# Modulo_MotorDC.net
KiCad netlist of a schematic drawn in Altium Designer
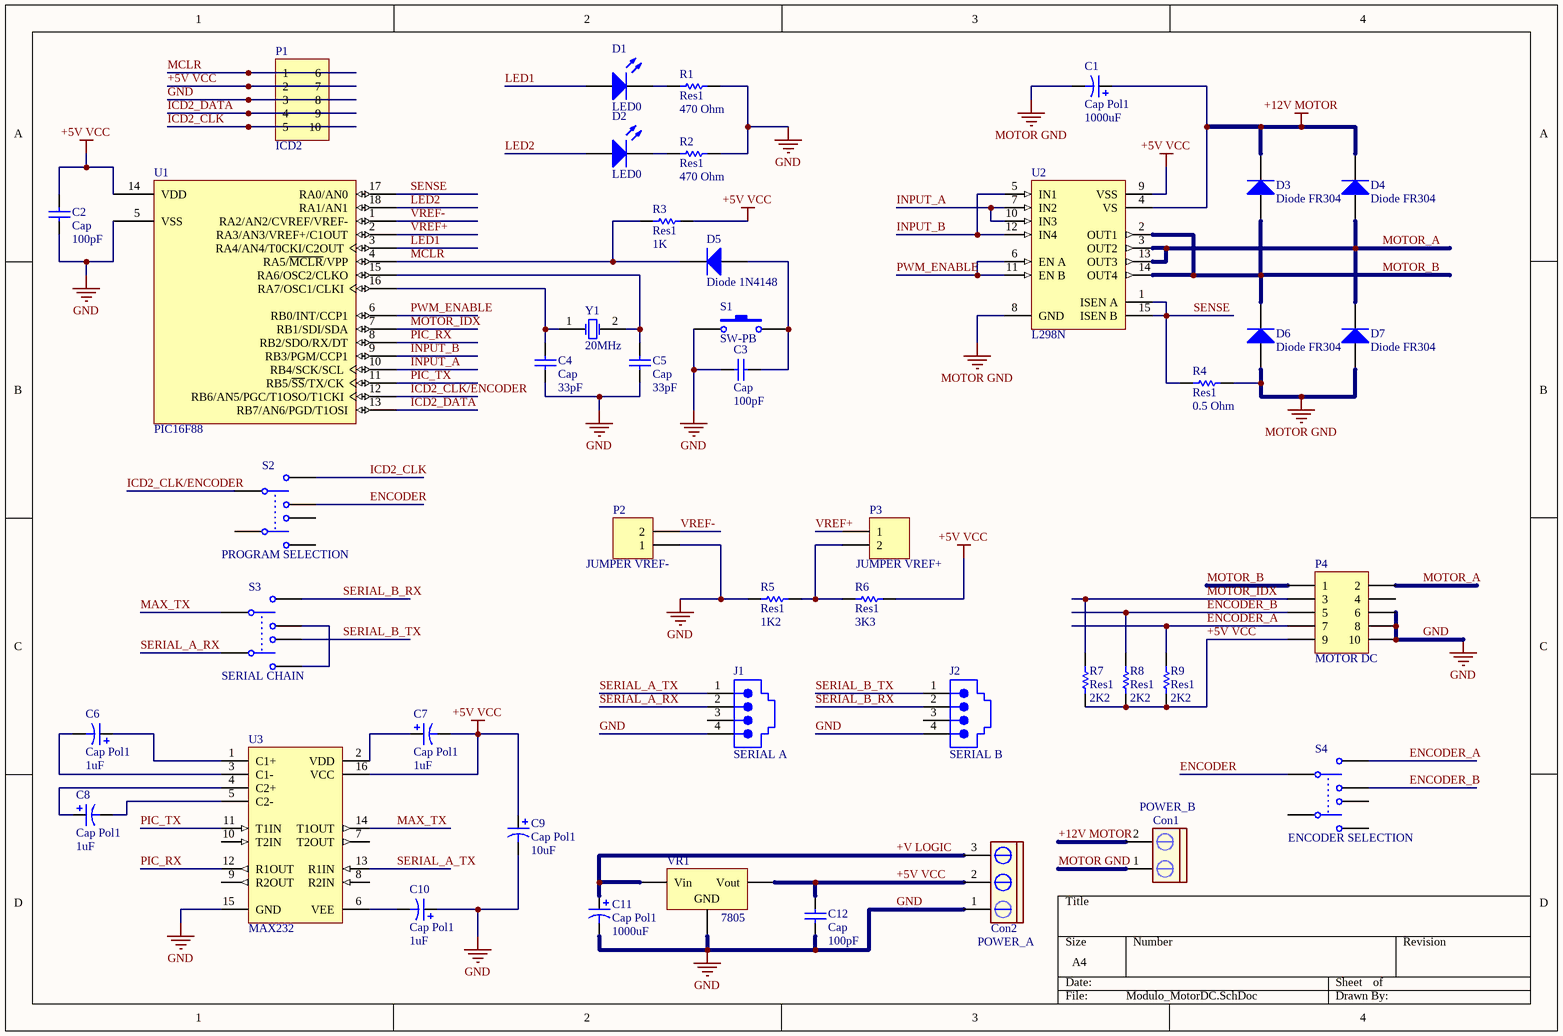
[diagram p0: Modulo_MotorDC.SchDoc]

(export (version "E")
  (design (tool "Eeschema 10.0.6"))
  (components
    (comp (ref "C1")
      (value "Cap Pol1")
      (footprint "RB5-10.5")
      (description "Polarized Capacitor (Radial)")
      (fields (field (name "ALTIUM_VALUE") "1000uF") (field (name "PUBLISHER") "Altium Limited"))
      (libsource (lib "Miscellaneous Devices") (part "Cap Pol1"))
    )
    (comp (ref "C2")
      (value "Cap")
      (footprint "CAPR2.54-5.1x3.2")
      (description "Capacitor")
      (fields (field (name "ALTIUM_VALUE") "100pF") (field (name "PUBLISHER") "Altium Limited"))
      (libsource (lib "Miscellaneous Devices") (part "Cap"))
    )
    (comp (ref "C3")
      (value "Cap")
      (footprint "CAPR2.54-5.1x3.2")
      (description "Capacitor")
      (fields (field (name "ALTIUM_VALUE") "100pF") (field (name "PUBLISHER") "Altium Limited"))
      (libsource (lib "Miscellaneous Devices") (part "Cap"))
    )
    (comp (ref "C4")
      (value "Cap")
      (footprint "CAPR2.54-5.1x3.2")
      (description "Capacitor")
      (fields (field (name "ALTIUM_VALUE") "33pF") (field (name "PUBLISHER") "Altium Limited"))
      (libsource (lib "Miscellaneous Devices") (part "Cap"))
    )
    (comp (ref "C5")
      (value "Cap")
      (footprint "CAPR2.54-5.1x3.2")
      (description "Capacitor")
      (fields (field (name "ALTIUM_VALUE") "33pF") (field (name "PUBLISHER") "Altium Limited"))
      (libsource (lib "Miscellaneous Devices") (part "Cap"))
    )
    (comp (ref "C6")
      (value "Cap Pol1")
      (footprint "CAPPR2-5x6.8")
      (description "Polarized Capacitor (Radial)")
      (fields (field (name "ALTIUM_VALUE") "1uF") (field (name "PUBLISHER") "Altium Limited"))
      (libsource (lib "Miscellaneous Devices") (part "Cap Pol1"))
    )
    (comp (ref "C7")
      (value "Cap Pol1")
      (footprint "CAPPR2-5x6.8")
      (description "Polarized Capacitor (Radial)")
      (fields (field (name "ALTIUM_VALUE") "1uF") (field (name "PUBLISHER") "Altium Limited"))
      (libsource (lib "Miscellaneous Devices") (part "Cap Pol1"))
    )
    (comp (ref "C8")
      (value "Cap Pol1")
      (footprint "CAPPR2-5x6.8")
      (description "Polarized Capacitor (Radial)")
      (fields (field (name "ALTIUM_VALUE") "1uF") (field (name "PUBLISHER") "Altium Limited"))
      (libsource (lib "Miscellaneous Devices") (part "Cap Pol1"))
    )
    (comp (ref "C9")
      (value "Cap Pol1")
      (footprint "CAPPR2-5x6.8")
      (description "Polarized Capacitor (Radial)")
      (fields (field (name "ALTIUM_VALUE") "10uF") (field (name "PUBLISHER") "Altium Limited"))
      (libsource (lib "Miscellaneous Devices") (part "Cap Pol1"))
    )
    (comp (ref "C10")
      (value "Cap Pol1")
      (footprint "CAPPR2-5x6.8")
      (description "Polarized Capacitor (Radial)")
      (fields (field (name "ALTIUM_VALUE") "1uF") (field (name "PUBLISHER") "Altium Limited"))
      (libsource (lib "Miscellaneous Devices") (part "Cap Pol1"))
    )
    (comp (ref "C11")
      (value "Cap Pol1")
      (footprint "RB5-10.5")
      (description "Polarized Capacitor (Radial)")
      (fields (field (name "ALTIUM_VALUE") "1000uF") (field (name "PUBLISHER") "Altium Limited"))
      (libsource (lib "Miscellaneous Devices") (part "Cap Pol1"))
    )
    (comp (ref "C12")
      (value "Cap")
      (footprint "CAPR2.54-5.1x3.2")
      (description "Capacitor")
      (fields (field (name "ALTIUM_VALUE") "100pF") (field (name "PUBLISHER") "Altium Limited"))
      (libsource (lib "Miscellaneous Devices") (part "Cap"))
    )
    (comp (ref "Con1")
      (value "POWER_B")
      (footprint "My_CN2")
      (description "Connector blue screw")
      (libsource (lib "Protel_Library") (part "CON2 pin blue"))
    )
    (comp (ref "Con2")
      (value "POWER_A")
      (footprint "My_CN3")
      (description "Connector green screw")
      (libsource (lib "Protel_Library") (part "CON3 pin Green"))
    )
    (comp (ref "D1")
      (value "LED0")
      (footprint "LED-0")
      (description "Typical INFRARED GaAs LED")
      (fields (field (name "PUBLISHER") "Altium Limited"))
      (libsource (lib "Miscellaneous Devices") (part "LED0"))
    )
    (comp (ref "D2")
      (value "LED0")
      (footprint "LED-0")
      (description "Typical INFRARED GaAs LED")
      (fields (field (name "PUBLISHER") "Altium Limited"))
      (libsource (lib "Miscellaneous Devices") (part "LED0"))
    )
    (comp (ref "D3")
      (value "Diode FR304")
      (footprint "DIO18.84-9.6x5.6")
      (description "3 Amp General Purpose Rectifier")
      (fields (field (name "PUBLISHER") "Altium Limited"))
      (libsource (lib "Miscellaneous Devices") (part "Diode 1N5404"))
    )
    (comp (ref "D4")
      (value "Diode FR304")
      (footprint "DIO18.84-9.6x5.6")
      (description "3 Amp General Purpose Rectifier")
      (fields (field (name "PUBLISHER") "Altium Limited"))
      (libsource (lib "Miscellaneous Devices") (part "Diode 1N5404"))
    )
    (comp (ref "D5")
      (value "Diode 1N4148")
      (footprint "DIO7.1-3.9x1.9")
      (description "High Conductance Fast Diode")
      (fields (field (name "PUBLISHER") "Altium Limited"))
      (libsource (lib "Miscellaneous Devices") (part "Diode 1N4148"))
    )
    (comp (ref "D6")
      (value "Diode FR304")
      (footprint "DIO18.84-9.6x5.6")
      (description "3 Amp General Purpose Rectifier")
      (fields (field (name "PUBLISHER") "Altium Limited"))
      (libsource (lib "Miscellaneous Devices") (part "Diode 1N5404"))
    )
    (comp (ref "D7")
      (value "Diode FR304")
      (footprint "DIO18.84-9.6x5.6")
      (description "3 Amp General Purpose Rectifier")
      (fields (field (name "PUBLISHER") "Altium Limited"))
      (libsource (lib "Miscellaneous Devices") (part "Diode 1N5404"))
    )
    (comp (ref "J1")
      (value "SERIAL A")
      (footprint "15-43-6245")
      (description "Right Angle, Standard Profile, RJ45-Keyed, Flange Mount PCB Jack")
      (fields (field (name "PUBLISHER") "Altium Limited"))
      (libsource (lib "Molex Modular Jack Right Angle") (part "15-43-6245"))
    )
    (comp (ref "J2")
      (value "SERIAL B")
      (footprint "15-43-6245")
      (description "Right Angle, Standard Profile, RJ45-Keyed, Flange Mount PCB Jack")
      (fields (field (name "PUBLISHER") "Altium Limited"))
      (libsource (lib "Molex Modular Jack Right Angle") (part "15-43-6245"))
    )
    (comp (ref "P1")
      (value "ICD2")
      (footprint "HEADER10_5x2_B")
      (description "Header, 5-Pin, Dual row")
      (fields (field (name "PUBLISHER") "Altium Limited"))
      (libsource (lib "Miscellaneous Connectors") (part "Header 5X2A"))
    )
    (comp (ref "P2")
      (value "JUMPER VREF-")
      (footprint "HDR1X2")
      (description "Header, 2-Pin")
      (fields (field (name "PUBLISHER") "Altium Limited"))
      (libsource (lib "") (part "Header 2_1"))
    )
    (comp (ref "P3")
      (value "JUMPER VREF+")
      (footprint "HDR1X2")
      (description "Header, 2-Pin")
      (fields (field (name "PUBLISHER") "Altium Limited"))
      (libsource (lib "Miscellaneous Connectors") (part "Header 2"))
    )
    (comp (ref "P4")
      (value "MOTOR DC")
      (footprint "HEADER10_5x2_A")
      (description "Header, 5-Pin, Dual row")
      (fields (field (name "PUBLISHER") "Altium Limited"))
      (libsource (lib "Miscellaneous Connectors") (part "Header 5X2"))
    )
    (comp (ref "R1")
      (value "Res1")
      (footprint "AXIAL-0.3")
      (description "Resistor")
      (fields (field (name "ALTIUM_VALUE") "470 Ohm") (field (name "PUBLISHER") "Altium Limited"))
      (libsource (lib "Miscellaneous Devices") (part "Res1"))
    )
    (comp (ref "R2")
      (value "Res1")
      (footprint "AXIAL-0.3")
      (description "Resistor")
      (fields (field (name "ALTIUM_VALUE") "470 Ohm") (field (name "PUBLISHER") "Altium Limited"))
      (libsource (lib "Miscellaneous Devices") (part "Res1"))
    )
    (comp (ref "R3")
      (value "Res1")
      (footprint "AXIAL-0.3")
      (description "Resistor")
      (fields (field (name "ALTIUM_VALUE") "1K") (field (name "PUBLISHER") "Altium Limited"))
      (libsource (lib "Miscellaneous Devices") (part "Res1"))
    )
    (comp (ref "R4")
      (value "Res1")
      (footprint "AXIAL-0.3")
      (description "Resistor")
      (fields (field (name "ALTIUM_VALUE") "0.5 Ohm") (field (name "PUBLISHER") "Altium Limited"))
      (libsource (lib "Miscellaneous Devices") (part "Res1"))
    )
    (comp (ref "R5")
      (value "Res1")
      (footprint "AXIAL-0.3")
      (description "Resistor")
      (fields (field (name "ALTIUM_VALUE") "1K2") (field (name "PUBLISHER") "Altium Limited"))
      (libsource (lib "Miscellaneous Devices") (part "Res1"))
    )
    (comp (ref "R6")
      (value "Res1")
      (footprint "AXIAL-0.3")
      (description "Resistor")
      (fields (field (name "ALTIUM_VALUE") "3K3") (field (name "PUBLISHER") "Altium Limited"))
      (libsource (lib "Miscellaneous Devices") (part "Res1"))
    )
    (comp (ref "R7")
      (value "Res1")
      (footprint "AXIAL-0.3")
      (description "Resistor")
      (fields (field (name "ALTIUM_VALUE") "2K2") (field (name "PUBLISHER") "Altium Limited"))
      (libsource (lib "Miscellaneous Devices") (part "Res1"))
    )
    (comp (ref "R8")
      (value "Res1")
      (footprint "AXIAL-0.3")
      (description "Resistor")
      (fields (field (name "ALTIUM_VALUE") "2K2") (field (name "PUBLISHER") "Altium Limited"))
      (libsource (lib "Miscellaneous Devices") (part "Res1"))
    )
    (comp (ref "R9")
      (value "Res1")
      (footprint "AXIAL-0.3")
      (description "Resistor")
      (fields (field (name "ALTIUM_VALUE") "2K2") (field (name "PUBLISHER") "Altium Limited"))
      (libsource (lib "Miscellaneous Devices") (part "Res1"))
    )
    (comp (ref "S1")
      (value "SW-PB")
      (footprint "TS-063")
      (description "Switch")
      (fields (field (name "PUBLISHER") "Altium Limited"))
      (libsource (lib "Miscellaneous Devices") (part "SW-PB"))
    )
    (comp (ref "S2")
      (value "PROGRAM SELECTION")
      (footprint "LD-202mini")
      (description "Double-Pole, Double-Throw Switch")
      (fields (field (name "PUBLISHER") "Altium Limited"))
      (libsource (lib "Miscellaneous Devices") (part "SW-DPDT"))
    )
    (comp (ref "S3")
      (value "SERIAL CHAIN")
      (footprint "LD-202mini")
      (description "Double-Pole, Double-Throw Switch")
      (fields (field (name "PUBLISHER") "Altium Limited"))
      (libsource (lib "Miscellaneous Devices") (part "SW-DPDT"))
    )
    (comp (ref "S4")
      (value "ENCODER SELECTION")
      (footprint "LD-202mini")
      (description "Double-Pole, Double-Throw Switch")
      (fields (field (name "PUBLISHER") "Altium Limited"))
      (libsource (lib "Miscellaneous Devices") (part "SW-DPDT"))
    )
    (comp (ref "U1")
      (value "PIC16F88")
      (footprint "PDIP300-P18")
      (fields (field (name "PUBLISHER") "Altium Limited"))
      (libsource (lib "Microchip Microcontroller 8-Bit PIC16") (part "PIC16F88-E/P"))
    )
    (comp (ref "U2")
      (value "L298N")
      (footprint "Multiwatt15V")
      (description "Dual Full Bridge Driver")
      (fields (field (name "PUBLISHER") "Altium Limited"))
      (libsource (lib "ST Interface DC Motor Controller") (part "L298N"))
    )
    (comp (ref "U3")
      (value "MAX232")
      (footprint "PE16A")
      (description "+5V Powered, Multi-Channel RS-232 Driver/Receiver")
      (fields (field (name "PUBLISHER") "Altium Limited"))
      (libsource (lib "Maxim Communication Transceiver") (part "MAX232ACPE"))
    )
    (comp (ref "VR1")
      (value "7805")
      (footprint "My_TO-220")
      (description "Voltage Regulator")
      (fields (field (name "PUBLISHER") "Altium Limited"))
      (libsource (lib "Miscellaneous Devices") (part "Volt Reg"))
    )
    (comp (ref "Y1")
      (value "20MHz")
      (footprint "My_Crystal")
      (description "Crystal Oscillator")
      (fields (field (name "PUBLISHER") "Altium Limited"))
      (libsource (lib "Miscellaneous Devices") (part "XTAL"))
    )
  )
  (nets
    (net (code "1") (name "+5V VCC") (class "Default")
      (node (ref "C12") (pin "2") (pinfunction "2_2") (pintype "passive"))
      (node (ref "C2") (pin "2") (pinfunction "2_2") (pintype "passive"))
      (node (ref "C7") (pin "2") (pinfunction "2_2") (pintype "passive"))
      (node (ref "C9") (pin "1") (pinfunction "1_1") (pintype "passive"))
      (node (ref "Con2") (pin "2") (pinfunction "2_2") (pintype "passive"))
      (node (ref "P1") (pin "2") (pinfunction "2_2") (pintype "passive"))
      (node (ref "P1") (pin "7") (pinfunction "7_7") (pintype "passive"))
      (node (ref "P4") (pin "9") (pinfunction "9_9") (pintype "passive"))
      (node (ref "R3") (pin "2") (pinfunction "2_2") (pintype "passive"))
      (node (ref "R6") (pin "2") (pinfunction "2_2") (pintype "passive"))
      (node (ref "R7") (pin "1") (pinfunction "1_1") (pintype "passive"))
      (node (ref "R8") (pin "1") (pinfunction "1_1") (pintype "passive"))
      (node (ref "R9") (pin "1") (pinfunction "1_1") (pintype "passive"))
      (node (ref "U1") (pin "14") (pinfunction "VDD_14") (pintype "power_in"))
      (node (ref "U2") (pin "9") (pinfunction "VSS_9") (pintype "power_in"))
      (node (ref "U3") (pin "16") (pinfunction "VCC_16") (pintype "power_in"))
      (node (ref "VR1") (pin "3") (pinfunction "Vout_3") (pintype "passive"))
    )
    (net (code "2") (name "+12V MOTOR") (class "Default")
      (node (ref "C1") (pin "1") (pinfunction "1_1") (pintype "passive"))
      (node (ref "Con1") (pin "2") (pinfunction "2_2") (pintype "passive"))
      (node (ref "D3") (pin "2") (pinfunction "K_2") (pintype "passive"))
      (node (ref "D4") (pin "2") (pinfunction "K_2") (pintype "passive"))
      (node (ref "U2") (pin "4") (pinfunction "VS_4") (pintype "power_in"))
    )
    (net (code "3") (name "/+V LOGIC") (class "Default")
      (node (ref "C11") (pin "1") (pinfunction "1_1") (pintype "passive"))
      (node (ref "Con2") (pin "3") (pinfunction "3_3") (pintype "passive"))
      (node (ref "VR1") (pin "1") (pinfunction "Vin_1") (pintype "passive"))
    )
    (net (code "5") (name "/ENCODER") (class "Default")
      (node (ref "S2") (pin "3") (pinfunction "3_3") (pintype "passive"))
      (node (ref "S4") (pin "1") (pinfunction "1_1") (pintype "passive"))
    )
    (net (code "6") (name "/ENCODER_A") (class "Default")
      (node (ref "P4") (pin "7") (pinfunction "7_7") (pintype "passive"))
      (node (ref "R9") (pin "2") (pinfunction "2_2") (pintype "passive"))
      (node (ref "S4") (pin "2") (pinfunction "2_2") (pintype "passive"))
    )
    (net (code "7") (name "/ENCODER_B") (class "Default")
      (node (ref "P4") (pin "5") (pinfunction "5_5") (pintype "passive"))
      (node (ref "R8") (pin "2") (pinfunction "2_2") (pintype "passive"))
      (node (ref "S4") (pin "3") (pinfunction "3_3") (pintype "passive"))
    )
    (net (code "8") (name "/ICD2_CLK") (class "Default")
      (node (ref "P1") (pin "10") (pinfunction "10_10") (pintype "passive"))
      (node (ref "P1") (pin "5") (pinfunction "5_5") (pintype "passive"))
      (node (ref "S2") (pin "2") (pinfunction "2_2") (pintype "passive"))
    )
    (net (code "9") (name "/ICD2_CLK{slash}ENCODER") (class "Default")
      (node (ref "S2") (pin "1") (pinfunction "1_1") (pintype "passive"))
      (node (ref "U1") (pin "12") (pinfunction "RB6/AN5/PGC/T1OSO/T1CKI_12") (pintype "bidirectional"))
    )
    (net (code "10") (name "/ICD2_DATA") (class "Default")
      (node (ref "P1") (pin "4") (pinfunction "4_4") (pintype "passive"))
      (node (ref "P1") (pin "9") (pinfunction "9_9") (pintype "passive"))
      (node (ref "U1") (pin "13") (pinfunction "RB7/AN6/PGD/T1OSI_13") (pintype "bidirectional"))
    )
    (net (code "11") (name "/INPUT_A") (class "Default")
      (node (ref "U1") (pin "10") (pinfunction "RB4/SCK/SCL_10") (pintype "bidirectional"))
      (node (ref "U2") (pin "10") (pinfunction "IN3_10") (pintype "input"))
      (node (ref "U2") (pin "7") (pinfunction "IN2_7") (pintype "input"))
    )
    (net (code "12") (name "/INPUT_B") (class "Default")
      (node (ref "U1") (pin "9") (pinfunction "RB3/PGM/CCP1_9") (pintype "bidirectional"))
      (node (ref "U2") (pin "12") (pinfunction "IN4_12") (pintype "input"))
      (node (ref "U2") (pin "5") (pinfunction "IN1_5") (pintype "input"))
    )
    (net (code "13") (name "/LED1") (class "Default")
      (node (ref "D1") (pin "1") (pinfunction "A_1") (pintype "passive"))
      (node (ref "U1") (pin "3") (pinfunction "RA4/AN4/T0CKI/C2OUT_3") (pintype "bidirectional"))
    )
    (net (code "14") (name "/LED2") (class "Default")
      (node (ref "D2") (pin "1") (pinfunction "A_1") (pintype "passive"))
      (node (ref "U1") (pin "18") (pinfunction "RA1/AN1_18") (pintype "bidirectional"))
    )
    (net (code "15") (name "/MAX_TX") (class "Default")
      (node (ref "S3") (pin "1") (pinfunction "1_1") (pintype "passive"))
      (node (ref "U3") (pin "14") (pinfunction "T1OUT_14") (pintype "output"))
    )
    (net (code "16") (name "/MCLR") (class "Default")
      (node (ref "D5") (pin "2") (pinfunction "K_2") (pintype "passive"))
      (node (ref "P1") (pin "1") (pinfunction "1_1") (pintype "passive"))
      (node (ref "P1") (pin "6") (pinfunction "6_6") (pintype "passive"))
      (node (ref "R3") (pin "1") (pinfunction "1_1") (pintype "passive"))
      (node (ref "U1") (pin "4") (pinfunction "RA5/~{MCLR}/VPP_4") (pintype "bidirectional"))
    )
    (net (code "17") (name "/MOTOR_A") (class "Default")
      (node (ref "D4") (pin "1") (pinfunction "A_1") (pintype "passive"))
      (node (ref "D7") (pin "2") (pinfunction "K_2") (pintype "passive"))
      (node (ref "P4") (pin "2") (pinfunction "2_2") (pintype "passive"))
      (node (ref "U2") (pin "13") (pinfunction "OUT3_13") (pintype "output"))
      (node (ref "U2") (pin "3") (pinfunction "OUT2_3") (pintype "output"))
    )
    (net (code "18") (name "/MOTOR_B") (class "Default")
      (node (ref "D3") (pin "1") (pinfunction "A_1") (pintype "passive"))
      (node (ref "D6") (pin "2") (pinfunction "K_2") (pintype "passive"))
      (node (ref "P4") (pin "1") (pinfunction "1_1") (pintype "passive"))
      (node (ref "U2") (pin "14") (pinfunction "OUT4_14") (pintype "output"))
      (node (ref "U2") (pin "2") (pinfunction "OUT1_2") (pintype "output"))
    )
    (net (code "19") (name "/MOTOR_IDX") (class "Default")
      (node (ref "P4") (pin "3") (pinfunction "3_3") (pintype "passive"))
      (node (ref "R7") (pin "2") (pinfunction "2_2") (pintype "passive"))
      (node (ref "U1") (pin "7") (pinfunction "RB1/SDI/SDA_7") (pintype "bidirectional"))
    )
    (net (code "20") (name "/PIC_RX") (class "Default")
      (node (ref "U1") (pin "8") (pinfunction "RB2/SDO/RX/DT_8") (pintype "bidirectional"))
      (node (ref "U3") (pin "12") (pinfunction "R1OUT_12") (pintype "output"))
    )
    (net (code "21") (name "/PIC_TX") (class "Default")
      (node (ref "U1") (pin "11") (pinfunction "RB5/~{SS}/TX/CK_11") (pintype "bidirectional"))
      (node (ref "U3") (pin "11") (pinfunction "T1IN_11") (pintype "input"))
    )
    (net (code "22") (name "/PWM_ENABLE") (class "Default")
      (node (ref "U1") (pin "6") (pinfunction "RB0/INT/CCP1_6") (pintype "bidirectional"))
      (node (ref "U2") (pin "11") (pinfunction "EN_B_11") (pintype "input"))
      (node (ref "U2") (pin "6") (pinfunction "EN_A_6") (pintype "input"))
    )
    (net (code "23") (name "/SENSE") (class "Default")
      (node (ref "R4") (pin "1") (pinfunction "1_1") (pintype "passive"))
      (node (ref "U1") (pin "17") (pinfunction "RA0/AN0_17") (pintype "bidirectional"))
      (node (ref "U2") (pin "1") (pinfunction "ISEN_A_1") (pintype "passive"))
      (node (ref "U2") (pin "15") (pinfunction "ISEN_B_15") (pintype "passive"))
    )
    (net (code "24") (name "/SERIAL_A_RX") (class "Default")
      (node (ref "J1") (pin "2") (pinfunction "2_2") (pintype "passive"))
      (node (ref "S3") (pin "4") (pinfunction "4_4") (pintype "passive"))
    )
    (net (code "25") (name "/SERIAL_A_TX") (class "Default")
      (node (ref "J1") (pin "1") (pinfunction "1_1") (pintype "passive"))
      (node (ref "U3") (pin "13") (pinfunction "R1IN_13") (pintype "input"))
    )
    (net (code "26") (name "/SERIAL_B_RX") (class "Default")
      (node (ref "J2") (pin "2") (pinfunction "2_2") (pintype "passive"))
      (node (ref "S3") (pin "2") (pinfunction "2_2") (pintype "passive"))
    )
    (net (code "27") (name "/SERIAL_B_TX") (class "Default")
      (node (ref "J2") (pin "1") (pinfunction "1_1") (pintype "passive"))
      (node (ref "S3") (pin "5") (pinfunction "5_5") (pintype "passive"))
    )
    (net (code "28") (name "/VREF+") (class "Default")
      (node (ref "P3") (pin "1") (pinfunction "1_1") (pintype "passive"))
      (node (ref "U1") (pin "2") (pinfunction "RA3/AN3/VREF+/C1OUT_2") (pintype "bidirectional"))
    )
    (net (code "29") (name "/VREF-") (class "Default")
      (node (ref "P2") (pin "2") (pinfunction "2_2") (pintype "passive"))
      (node (ref "U1") (pin "1") (pinfunction "RA2/AN2/CVREF/VREF-_1") (pintype "bidirectional"))
    )
    (net (code "30") (name "GND") (class "Default")
      (node (ref "C10") (pin "1") (pinfunction "1_1") (pintype "passive"))
      (node (ref "C11") (pin "2") (pinfunction "2_2") (pintype "passive"))
      (node (ref "C12") (pin "1") (pinfunction "1_1") (pintype "passive"))
      (node (ref "C2") (pin "1") (pinfunction "1_1") (pintype "passive"))
      (node (ref "C3") (pin "1") (pinfunction "1_1") (pintype "passive"))
      (node (ref "C4") (pin "1") (pinfunction "1_1") (pintype "passive"))
      (node (ref "C5") (pin "1") (pinfunction "1_1") (pintype "passive"))
      (node (ref "C9") (pin "2") (pinfunction "2_2") (pintype "passive"))
      (node (ref "Con2") (pin "1") (pinfunction "1_1") (pintype "passive"))
      (node (ref "J1") (pin "4") (pinfunction "4_4") (pintype "passive"))
      (node (ref "J2") (pin "4") (pinfunction "4_4") (pintype "passive"))
      (node (ref "P1") (pin "3") (pinfunction "3_3") (pintype "passive"))
      (node (ref "P1") (pin "8") (pinfunction "8_8") (pintype "passive"))
      (node (ref "P2") (pin "1") (pinfunction "1_1") (pintype "passive"))
      (node (ref "P4") (pin "10") (pinfunction "10_10") (pintype "passive"))
      (node (ref "P4") (pin "6") (pinfunction "6_6") (pintype "passive"))
      (node (ref "P4") (pin "8") (pinfunction "8_8") (pintype "passive"))
      (node (ref "R1") (pin "2") (pinfunction "2_2") (pintype "passive"))
      (node (ref "R2") (pin "2") (pinfunction "2_2") (pintype "passive"))
      (node (ref "R5") (pin "1") (pinfunction "1_1") (pintype "passive"))
      (node (ref "S1") (pin "1") (pinfunction "1_1") (pintype "passive"))
      (node (ref "U1") (pin "5") (pinfunction "VSS_5") (pintype "power_in"))
      (node (ref "U3") (pin "15") (pinfunction "GND_15") (pintype "power_in"))
      (node (ref "VR1") (pin "2") (pinfunction "GND_2") (pintype "passive"))
    )
    (net (code "31") (name "MOTOR GND") (class "Default")
      (node (ref "C1") (pin "2") (pinfunction "2_2") (pintype "passive"))
      (node (ref "Con1") (pin "1") (pinfunction "1_1") (pintype "passive"))
      (node (ref "D6") (pin "1") (pinfunction "A_1") (pintype "passive"))
      (node (ref "D7") (pin "1") (pinfunction "A_1") (pintype "passive"))
      (node (ref "R4") (pin "2") (pinfunction "2_2") (pintype "passive"))
      (node (ref "U2") (pin "8") (pinfunction "GND_8") (pintype "power_in"))
    )
    (net (code "32") (name "Net-(D1-K)") (class "Default")
      (node (ref "D1") (pin "2") (pinfunction "K_2") (pintype "passive"))
      (node (ref "R1") (pin "1") (pinfunction "1_1") (pintype "passive"))
    )
    (net (code "33") (name "Net-(D2-K)") (class "Default")
      (node (ref "D2") (pin "2") (pinfunction "K_2") (pintype "passive"))
      (node (ref "R2") (pin "1") (pinfunction "1_1") (pintype "passive"))
    )
    (net (code "34") (name "Net-(D5-A)") (class "Default")
      (node (ref "C3") (pin "2") (pinfunction "2_2") (pintype "passive"))
      (node (ref "D5") (pin "1") (pinfunction "A_1") (pintype "passive"))
      (node (ref "S1") (pin "2") (pinfunction "2_2") (pintype "passive"))
    )
    (net (code "35") (name "Net-(P3-Pad2)") (class "Default")
      (node (ref "P3") (pin "2") (pinfunction "2_2") (pintype "passive"))
      (node (ref "R5") (pin "2") (pinfunction "2_2") (pintype "passive"))
      (node (ref "R6") (pin "1") (pinfunction "1_1") (pintype "passive"))
    )
    (net (code "36") (name "Net-(S3-Pad3)") (class "Default")
      (node (ref "S3") (pin "3") (pinfunction "3_3") (pintype "passive"))
      (node (ref "S3") (pin "6") (pinfunction "6_6") (pintype "passive"))
    )
    (net (code "37") (name "Net-(U1-RA6{slash}OSC2{slash}CLKO)") (class "Default")
      (node (ref "C5") (pin "2") (pinfunction "2_2") (pintype "passive"))
      (node (ref "U1") (pin "15") (pinfunction "RA6/OSC2/CLKO_15") (pintype "bidirectional"))
      (node (ref "Y1") (pin "2") (pinfunction "OSC2_2") (pintype "passive"))
    )
    (net (code "38") (name "Net-(U1-RA7{slash}OSC1{slash}CLKI)") (class "Default")
      (node (ref "C4") (pin "2") (pinfunction "2_2") (pintype "passive"))
      (node (ref "U1") (pin "16") (pinfunction "RA7/OSC1/CLKI_16") (pintype "bidirectional"))
      (node (ref "Y1") (pin "1") (pinfunction "OSC1_1") (pintype "passive"))
    )
    (net (code "39") (name "Net-(U3-C1+)") (class "Default")
      (node (ref "C6") (pin "1") (pinfunction "1_1") (pintype "passive"))
      (node (ref "U3") (pin "1") (pinfunction "C1+_1") (pintype "passive"))
    )
    (net (code "40") (name "Net-(U3-C1-)") (class "Default")
      (node (ref "C6") (pin "2") (pinfunction "2_2") (pintype "passive"))
      (node (ref "U3") (pin "3") (pinfunction "C1-_3") (pintype "passive"))
    )
    (net (code "41") (name "Net-(U3-C2+)") (class "Default")
      (node (ref "C8") (pin "1") (pinfunction "1_1") (pintype "passive"))
      (node (ref "U3") (pin "4") (pinfunction "C2+_4") (pintype "passive"))
    )
    (net (code "42") (name "Net-(U3-C2-)") (class "Default")
      (node (ref "C8") (pin "2") (pinfunction "2_2") (pintype "passive"))
      (node (ref "U3") (pin "5") (pinfunction "C2-_5") (pintype "passive"))
    )
    (net (code "43") (name "Net-(U3-VDD)") (class "Default")
      (node (ref "C7") (pin "1") (pinfunction "1_1") (pintype "passive"))
      (node (ref "U3") (pin "2") (pinfunction "VDD_2") (pintype "power_in"))
    )
    (net (code "44") (name "Net-(U3-VEE)") (class "Default")
      (node (ref "C10") (pin "2") (pinfunction "2_2") (pintype "passive"))
      (node (ref "U3") (pin "6") (pinfunction "VEE_6") (pintype "power_in"))
    )
    (net (code "45") (name "unconnected-(J1-Pad3)") (class "Default")
      (node (ref "J1") (pin "3") (pinfunction "3_3") (pintype "passive"))
    )
    (net (code "46") (name "unconnected-(J2-Pad3)") (class "Default")
      (node (ref "J2") (pin "3") (pinfunction "3_3") (pintype "passive"))
    )
    (net (code "47") (name "unconnected-(P4-Pad4)") (class "Default")
      (node (ref "P4") (pin "4") (pinfunction "4_4") (pintype "passive"))
    )
    (net (code "48") (name "unconnected-(S2-Pad4)") (class "Default")
      (node (ref "S2") (pin "4") (pinfunction "4_4") (pintype "passive"))
    )
    (net (code "49") (name "unconnected-(S2-Pad5)") (class "Default")
      (node (ref "S2") (pin "5") (pinfunction "5_5") (pintype "passive"))
    )
    (net (code "50") (name "unconnected-(S2-Pad6)") (class "Default")
      (node (ref "S2") (pin "6") (pinfunction "6_6") (pintype "passive"))
    )
    (net (code "51") (name "unconnected-(S4-Pad4)") (class "Default")
      (node (ref "S4") (pin "4") (pinfunction "4_4") (pintype "passive"))
    )
    (net (code "52") (name "unconnected-(S4-Pad5)") (class "Default")
      (node (ref "S4") (pin "5") (pinfunction "5_5") (pintype "passive"))
    )
    (net (code "53") (name "unconnected-(S4-Pad6)") (class "Default")
      (node (ref "S4") (pin "6") (pinfunction "6_6") (pintype "passive"))
    )
    (net (code "54") (name "unconnected-(U3-R2IN-Pad8)") (class "Default")
      (node (ref "U3") (pin "8") (pinfunction "R2IN_8") (pintype "input"))
    )
    (net (code "55") (name "unconnected-(U3-R2OUT-Pad9)") (class "Default")
      (node (ref "U3") (pin "9") (pinfunction "R2OUT_9") (pintype "output"))
    )
    (net (code "56") (name "unconnected-(U3-T2IN-Pad10)") (class "Default")
      (node (ref "U3") (pin "10") (pinfunction "T2IN_10") (pintype "input"))
    )
    (net (code "57") (name "unconnected-(U3-T2OUT-Pad7)") (class "Default")
      (node (ref "U3") (pin "7") (pinfunction "T2OUT_7") (pintype "output"))
    )
  )
)
